# MakerstudioTrainingBoard.net
KiCad netlist of a schematic drawn in EAGLE
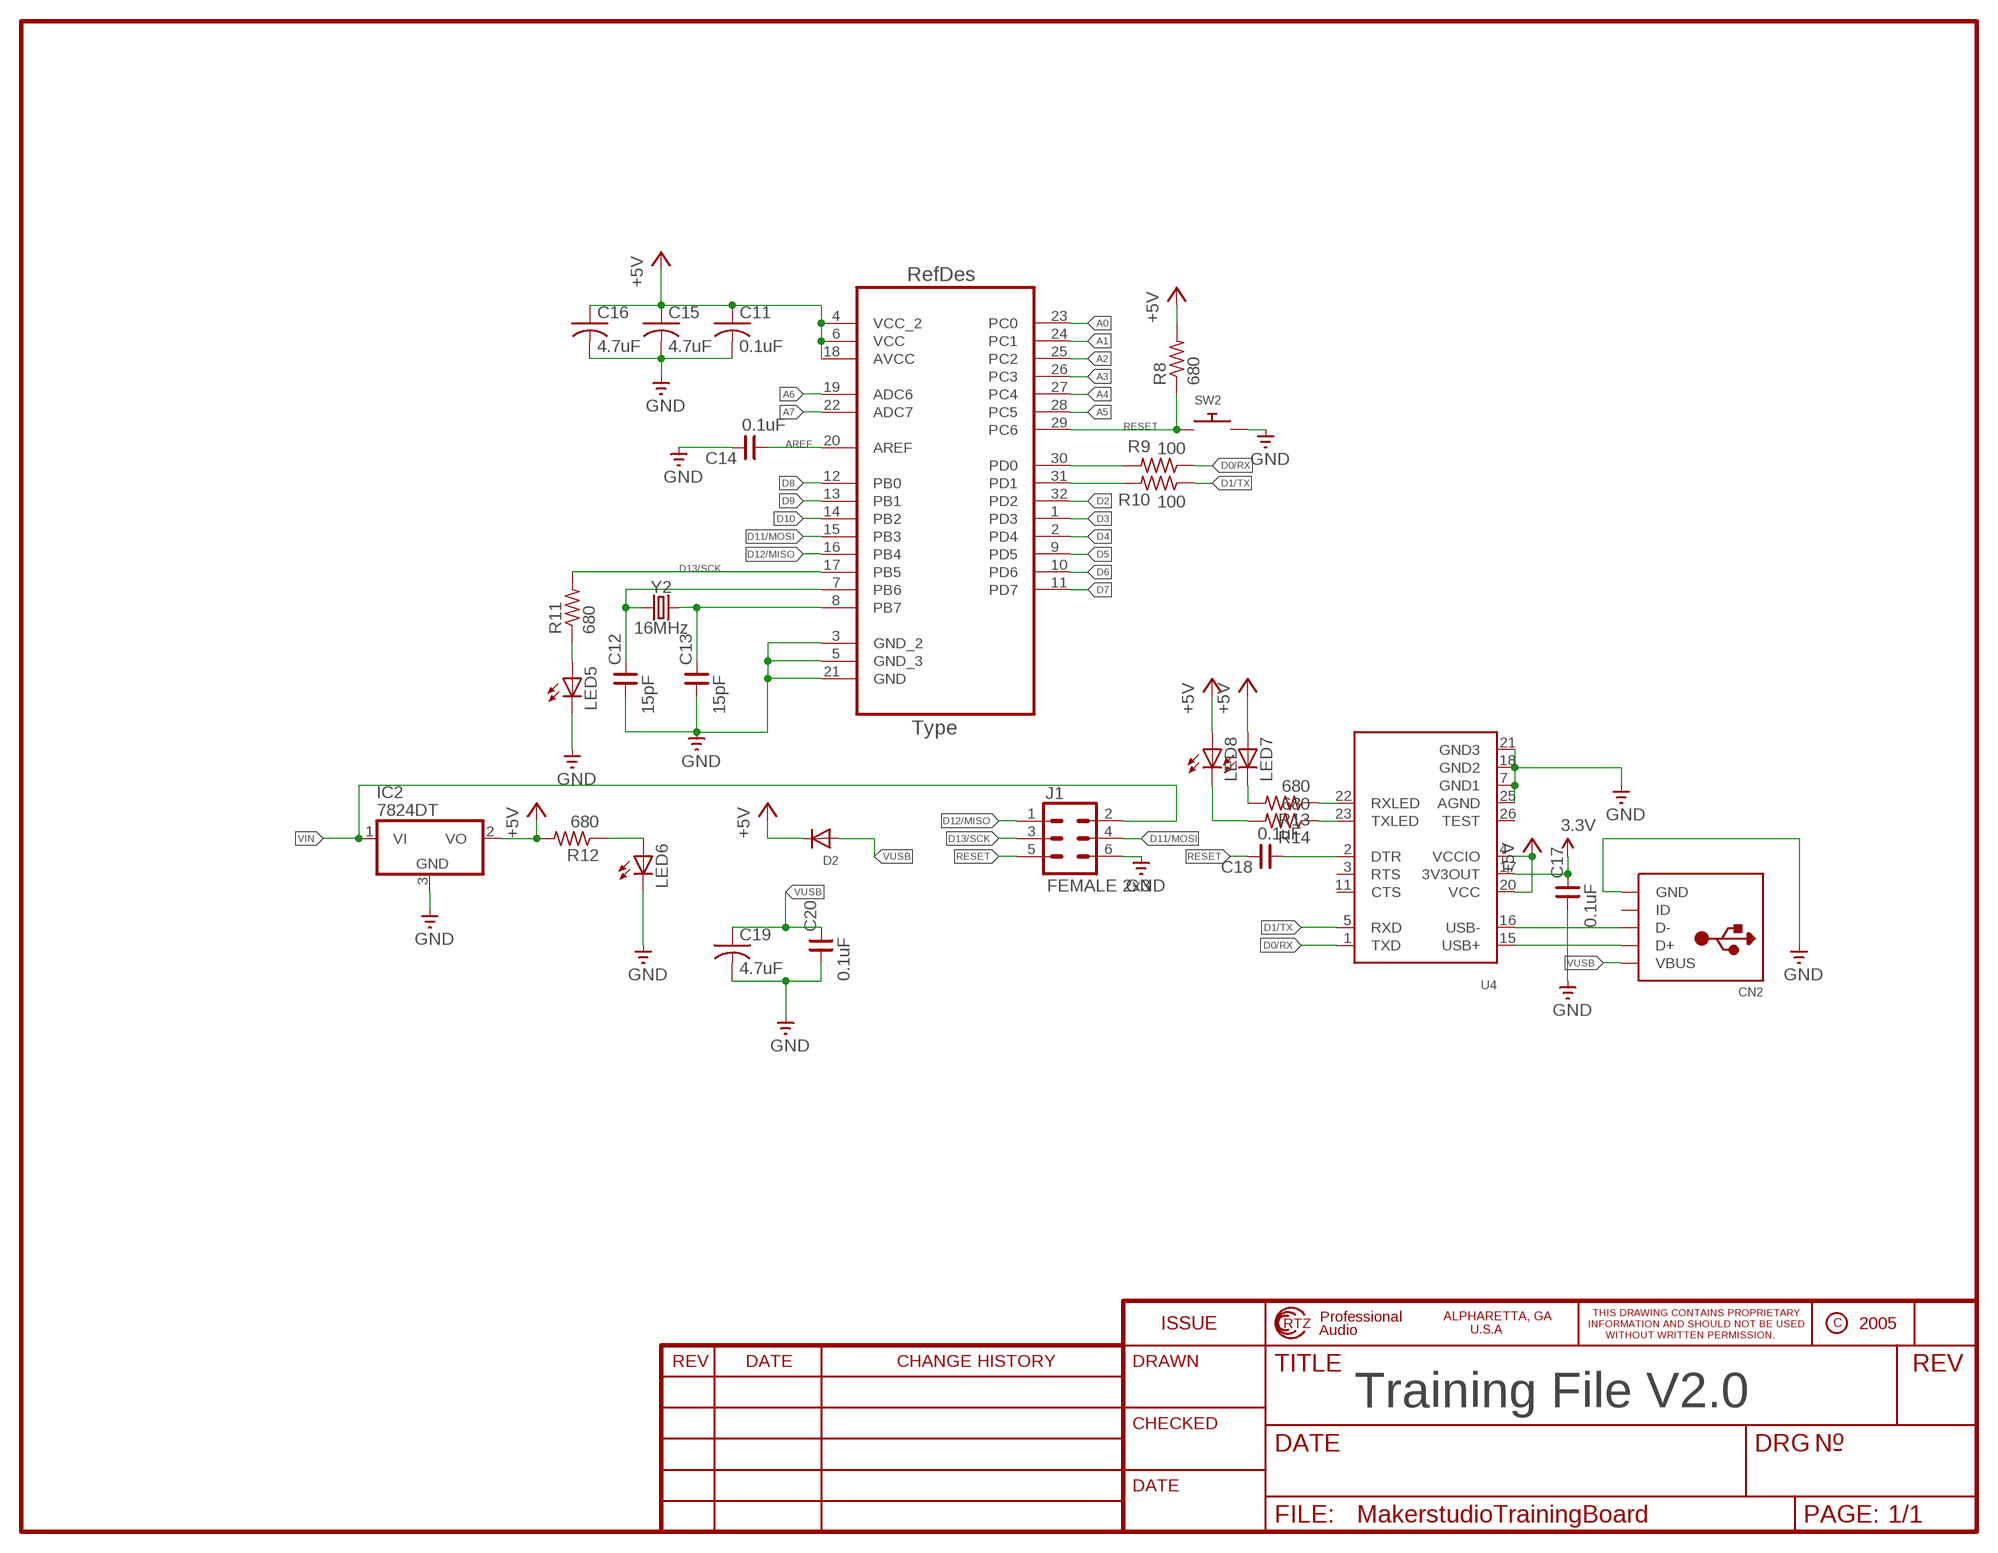
[diagram p0: schematic, sheet 1]

(export (version "E")
  (design (tool "Eeschema 10.0.6"))
  (components
    (comp (ref "C11")
      (value "0.1uF")
      (footprint "eagle-import:C0805")
      (libsource (lib "eagle-import") (part "C-USC0805"))
    )
    (comp (ref "C12")
      (value "15pF")
      (footprint "eagle-import:0805")
      (libsource (lib "eagle-import") (part "CNP-0805"))
    )
    (comp (ref "C13")
      (value "15pF")
      (footprint "eagle-import:0805")
      (libsource (lib "eagle-import") (part "CNP-0805"))
    )
    (comp (ref "C14")
      (value "0.1uF")
      (footprint "eagle-import:0805")
      (libsource (lib "eagle-import") (part "CNP-0805"))
    )
    (comp (ref "C15")
      (value "4.7uF")
      (footprint "eagle-import:C0805")
      (libsource (lib "eagle-import") (part "C-USC0805"))
    )
    (comp (ref "C16")
      (value "4.7uF")
      (footprint "eagle-import:C0805")
      (libsource (lib "eagle-import") (part "C-USC0805"))
    )
    (comp (ref "C17")
      (value "0.1uF")
      (footprint "eagle-import:0805")
      (libsource (lib "eagle-import") (part "CNP-0805"))
    )
    (comp (ref "C18")
      (value "0.1uF")
      (footprint "eagle-import:0805")
      (libsource (lib "eagle-import") (part "CNP-0805"))
    )
    (comp (ref "C19")
      (value "4.7uF")
      (footprint "eagle-import:C0805")
      (libsource (lib "eagle-import") (part "C-USC0805"))
    )
    (comp (ref "C20")
      (value "0.1uF")
      (footprint "eagle-import:0805")
      (libsource (lib "eagle-import") (part "CNP-0805"))
    )
    (comp (ref "CN2")
      (value "USBMINIB")
      (footprint "eagle-import:USB-MINIB")
      (libsource (lib "eagle-import") (part "USBMINIB"))
    )
    (comp (ref "D2")
      (value "DIODESOD-123")
      (footprint "eagle-import:SOD-123")
      (libsource (lib "eagle-import") (part "DIODESOD-123"))
    )
    (comp (ref "IC2")
      (value "7824DT")
      (footprint "eagle-import:TO252")
      (libsource (lib "eagle-import") (part "78DT24"))
    )
    (comp (ref "J1")
      (value "FEMALE 2x3")
      (footprint "eagle-import:2X3")
      (libsource (lib "eagle-import") (part "CONN_03X2FEMALE"))
    )
    (comp (ref "LED5")
      (value "LEDCHIPLED_0805")
      (footprint "eagle-import:CHIPLED_0805")
      (libsource (lib "eagle-import") (part "LEDCHIPLED_0805"))
    )
    (comp (ref "LED6")
      (value "LEDCHIPLED_0805")
      (footprint "eagle-import:CHIPLED_0805")
      (libsource (lib "eagle-import") (part "LEDCHIPLED_0805"))
    )
    (comp (ref "LED7")
      (value "LEDCHIPLED_0805")
      (footprint "eagle-import:CHIPLED_0805")
      (libsource (lib "eagle-import") (part "LEDCHIPLED_0805"))
    )
    (comp (ref "LED8")
      (value "LEDCHIPLED_0805")
      (footprint "eagle-import:CHIPLED_0805")
      (libsource (lib "eagle-import") (part "LEDCHIPLED_0805"))
    )
    (comp (ref "R8")
      (value "680")
      (footprint "eagle-import:R0805")
      (libsource (lib "eagle-import") (part "R-US_R0805"))
    )
    (comp (ref "R9")
      (value "100")
      (footprint "eagle-import:R0805")
      (libsource (lib "eagle-import") (part "R-US_R0805"))
    )
    (comp (ref "R10")
      (value "100")
      (footprint "eagle-import:R0805")
      (libsource (lib "eagle-import") (part "R-US_R0805"))
    )
    (comp (ref "R11")
      (value "680")
      (footprint "eagle-import:R0805")
      (libsource (lib "eagle-import") (part "R-US_R0805"))
    )
    (comp (ref "R12")
      (value "680")
      (footprint "eagle-import:R0805")
      (libsource (lib "eagle-import") (part "R-US_R0805"))
    )
    (comp (ref "R13")
      (value "680")
      (footprint "eagle-import:R0805")
      (libsource (lib "eagle-import") (part "R-US_R0805"))
    )
    (comp (ref "R14")
      (value "680")
      (footprint "eagle-import:R0805")
      (libsource (lib "eagle-import") (part "R-US_R0805"))
    )
    (comp (ref "SW2")
      (value "SWITCH_PUSHBUTTONEVQ-PE")
      (footprint "eagle-import:TACT_PANA-EVQ")
      (libsource (lib "eagle-import") (part "SWITCH_PUSHBUTTONEVQ-PE"))
    )
    (comp (ref "U3")
      (value "ATMEGA328P-AU")
      (footprint "eagle-import:QFP80P900X900X120-32N")
      (libsource (lib "eagle-import") (part "ATMEGA328P-AU"))
    )
    (comp (ref "U4")
      (value "FT232RLSSOP28")
      (footprint "eagle-import:SSOP28DB")
      (libsource (lib "eagle-import") (part "FT232RLSSOP28"))
    )
    (comp (ref "Y2")
      (value "16MHz")
      (footprint "eagle-import:HC49US")
      (libsource (lib "eagle-import") (part "CRYSTAL-16MHZPTH-HC49US"))
    )
  )
  (nets
    (net (code "1") (name "+5V") (class "Default")
      (node (ref "C11") (pin "1") (pinfunction "1_1") (pintype "passive"))
      (node (ref "C15") (pin "1") (pinfunction "1_1") (pintype "passive"))
      (node (ref "C16") (pin "1") (pinfunction "1_1") (pintype "passive"))
      (node (ref "D2") (pin "C") (pinfunction "C_C") (pintype "passive"))
      (node (ref "IC2") (pin "2") (pinfunction "VO_2") (pintype "passive"))
      (node (ref "LED7") (pin "A") (pinfunction "A_A") (pintype "passive"))
      (node (ref "LED8") (pin "A") (pinfunction "A_A") (pintype "passive"))
      (node (ref "R12") (pin "2") (pinfunction "2_2") (pintype "passive"))
      (node (ref "R8") (pin "2") (pinfunction "2_2") (pintype "passive"))
      (node (ref "U3") (pin "18") (pinfunction "AVCC_18") (pintype "power_in"))
      (node (ref "U3") (pin "4") (pinfunction "VCC_2_4") (pintype "power_in"))
      (node (ref "U3") (pin "6") (pinfunction "VCC_6") (pintype "power_in"))
      (node (ref "U4") (pin "20") (pinfunction "VCC_20") (pintype "power_in"))
      (node (ref "U4") (pin "4") (pinfunction "VCCIO_4") (pintype "power_in"))
    )
    (net (code "2") (name "/AREF") (class "Default")
      (node (ref "C14") (pin "1") (pinfunction "1_1") (pintype "passive"))
      (node (ref "U3") (pin "20") (pinfunction "AREF_20") (pintype "input"))
    )
    (net (code "3") (name "3.3V") (class "Default")
      (node (ref "C17") (pin "2") (pinfunction "2_2") (pintype "passive"))
      (node (ref "U4") (pin "17") (pinfunction "3V3OUT_17") (pintype "power_in"))
    )
    (net (code "4") (name "A0") (class "Default")
      (node (ref "U3") (pin "23") (pinfunction "PC0_23") (pintype "bidirectional"))
    )
    (net (code "5") (name "A1") (class "Default")
      (node (ref "U3") (pin "24") (pinfunction "PC1_24") (pintype "bidirectional"))
    )
    (net (code "6") (name "A2") (class "Default")
      (node (ref "U3") (pin "25") (pinfunction "PC2_25") (pintype "bidirectional"))
    )
    (net (code "7") (name "A3") (class "Default")
      (node (ref "U3") (pin "26") (pinfunction "PC3_26") (pintype "bidirectional"))
    )
    (net (code "8") (name "A4") (class "Default")
      (node (ref "U3") (pin "27") (pinfunction "PC4_27") (pintype "bidirectional"))
    )
    (net (code "9") (name "A5") (class "Default")
      (node (ref "U3") (pin "28") (pinfunction "PC5_28") (pintype "bidirectional"))
    )
    (net (code "10") (name "A6") (class "Default")
      (node (ref "U3") (pin "19") (pinfunction "ADC6_19") (pintype "input"))
    )
    (net (code "11") (name "A7") (class "Default")
      (node (ref "U3") (pin "22") (pinfunction "ADC7_22") (pintype "input"))
    )
    (net (code "12") (name "D0{slash}RX") (class "Default")
      (node (ref "R9") (pin "1") (pinfunction "1_1") (pintype "passive"))
      (node (ref "U4") (pin "1") (pinfunction "TXD_1") (pintype "output"))
    )
    (net (code "13") (name "D1{slash}TX") (class "Default")
      (node (ref "R10") (pin "1") (pinfunction "1_1") (pintype "passive"))
      (node (ref "U4") (pin "5") (pinfunction "RXD_5") (pintype "input"))
    )
    (net (code "14") (name "D2") (class "Default")
      (node (ref "U3") (pin "32") (pinfunction "PD2_32") (pintype "bidirectional"))
    )
    (net (code "15") (name "D3") (class "Default")
      (node (ref "U3") (pin "1") (pinfunction "PD3_1") (pintype "bidirectional"))
    )
    (net (code "16") (name "D4") (class "Default")
      (node (ref "U3") (pin "2") (pinfunction "PD4_2") (pintype "bidirectional"))
    )
    (net (code "17") (name "D5") (class "Default")
      (node (ref "U3") (pin "9") (pinfunction "PD5_9") (pintype "bidirectional"))
    )
    (net (code "18") (name "D6") (class "Default")
      (node (ref "U3") (pin "10") (pinfunction "PD6_10") (pintype "bidirectional"))
    )
    (net (code "19") (name "D7") (class "Default")
      (node (ref "U3") (pin "11") (pinfunction "PD7_11") (pintype "bidirectional"))
    )
    (net (code "20") (name "D8") (class "Default")
      (node (ref "U3") (pin "12") (pinfunction "PB0_12") (pintype "bidirectional"))
    )
    (net (code "21") (name "D9") (class "Default")
      (node (ref "U3") (pin "13") (pinfunction "PB1_13") (pintype "bidirectional"))
    )
    (net (code "22") (name "D10") (class "Default")
      (node (ref "U3") (pin "14") (pinfunction "PB2_14") (pintype "bidirectional"))
    )
    (net (code "23") (name "D11{slash}MOSI") (class "Default")
      (node (ref "J1") (pin "4") (pinfunction "4_4") (pintype "bidirectional"))
      (node (ref "U3") (pin "15") (pinfunction "PB3_15") (pintype "bidirectional"))
    )
    (net (code "24") (name "D12{slash}MISO") (class "Default")
      (node (ref "J1") (pin "1") (pinfunction "1_1") (pintype "bidirectional"))
      (node (ref "U3") (pin "16") (pinfunction "PB4_16") (pintype "bidirectional"))
    )
    (net (code "25") (name "D13{slash}SCK") (class "Default")
      (node (ref "J1") (pin "3") (pinfunction "3_3") (pintype "bidirectional"))
      (node (ref "R11") (pin "2") (pinfunction "2_2") (pintype "passive"))
      (node (ref "U3") (pin "17") (pinfunction "PB5_17") (pintype "bidirectional"))
    )
    (net (code "26") (name "GND") (class "Default")
      (node (ref "C11") (pin "2") (pinfunction "2_2") (pintype "passive"))
      (node (ref "C12") (pin "1") (pinfunction "1_1") (pintype "passive"))
      (node (ref "C13") (pin "1") (pinfunction "1_1") (pintype "passive"))
      (node (ref "C14") (pin "2") (pinfunction "2_2") (pintype "passive"))
      (node (ref "C15") (pin "2") (pinfunction "2_2") (pintype "passive"))
      (node (ref "C16") (pin "2") (pinfunction "2_2") (pintype "passive"))
      (node (ref "C17") (pin "1") (pinfunction "1_1") (pintype "passive"))
      (node (ref "C19") (pin "2") (pinfunction "2_2") (pintype "passive"))
      (node (ref "C20") (pin "1") (pinfunction "1_1") (pintype "passive"))
      (node (ref "CN2") (pin "GND") (pinfunction "GND_GND") (pintype "power_in"))
      (node (ref "IC2") (pin "3") (pinfunction "GND_3") (pintype "passive"))
      (node (ref "J1") (pin "6") (pinfunction "6_6") (pintype "bidirectional"))
      (node (ref "LED5") (pin "C") (pinfunction "C_C") (pintype "passive"))
      (node (ref "LED6") (pin "C") (pinfunction "C_C") (pintype "passive"))
      (node (ref "SW2") (pin "P$2") (pinfunction "P$2_P$2") (pintype "passive"))
      (node (ref "U3") (pin "21") (pinfunction "GND_21") (pintype "passive"))
      (node (ref "U3") (pin "3") (pinfunction "GND_2_3") (pintype "passive"))
      (node (ref "U3") (pin "5") (pinfunction "GND_3_5") (pintype "passive"))
      (node (ref "U4") (pin "18") (pinfunction "GND2_18") (pintype "power_in"))
      (node (ref "U4") (pin "21") (pinfunction "GND3_21") (pintype "power_in"))
      (node (ref "U4") (pin "25") (pinfunction "AGND_25") (pintype "power_in"))
      (node (ref "U4") (pin "7") (pinfunction "GND1_7") (pintype "power_in"))
    )
    (net (code "27") (name "Net-(LED5-PadA)") (class "Default")
      (node (ref "LED5") (pin "A") (pinfunction "A_A") (pintype "passive"))
      (node (ref "R11") (pin "1") (pinfunction "1_1") (pintype "passive"))
    )
    (net (code "28") (name "Net-(LED6-PadA)") (class "Default")
      (node (ref "LED6") (pin "A") (pinfunction "A_A") (pintype "passive"))
      (node (ref "R12") (pin "1") (pinfunction "1_1") (pintype "passive"))
    )
    (net (code "29") (name "Net-(LED7-PadC)") (class "Default")
      (node (ref "LED7") (pin "C") (pinfunction "C_C") (pintype "passive"))
      (node (ref "R13") (pin "2") (pinfunction "2_2") (pintype "passive"))
    )
    (net (code "30") (name "Net-(LED8-PadC)") (class "Default")
      (node (ref "LED8") (pin "C") (pinfunction "C_C") (pintype "passive"))
      (node (ref "R14") (pin "2") (pinfunction "2_2") (pintype "passive"))
    )
    (net (code "31") (name "Net-(U3-PB6)") (class "Default")
      (node (ref "C12") (pin "2") (pinfunction "2_2") (pintype "passive"))
      (node (ref "U3") (pin "7") (pinfunction "PB6_7") (pintype "bidirectional"))
      (node (ref "Y2") (pin "1") (pinfunction "1_1") (pintype "passive"))
    )
    (net (code "32") (name "Net-(U3-PB7)") (class "Default")
      (node (ref "C13") (pin "2") (pinfunction "2_2") (pintype "passive"))
      (node (ref "U3") (pin "8") (pinfunction "PB7_8") (pintype "bidirectional"))
      (node (ref "Y2") (pin "2") (pinfunction "2_2") (pintype "passive"))
    )
    (net (code "33") (name "Net-(U3-PD0)") (class "Default")
      (node (ref "R9") (pin "2") (pinfunction "2_2") (pintype "passive"))
      (node (ref "U3") (pin "30") (pinfunction "PD0_30") (pintype "bidirectional"))
    )
    (net (code "34") (name "Net-(U3-PD1)") (class "Default")
      (node (ref "R10") (pin "2") (pinfunction "2_2") (pintype "passive"))
      (node (ref "U3") (pin "31") (pinfunction "PD1_31") (pintype "bidirectional"))
    )
    (net (code "35") (name "Net-(U4-DTR)") (class "Default")
      (node (ref "C18") (pin "1") (pinfunction "1_1") (pintype "passive"))
      (node (ref "U4") (pin "2") (pinfunction "DTR_2") (pintype "bidirectional"))
    )
    (net (code "36") (name "Net-(U4-RXLED)") (class "Default")
      (node (ref "R13") (pin "1") (pinfunction "1_1") (pintype "passive"))
      (node (ref "U4") (pin "22") (pinfunction "RXLED_22") (pintype "bidirectional"))
    )
    (net (code "37") (name "Net-(U4-TXLED)") (class "Default")
      (node (ref "R14") (pin "1") (pinfunction "1_1") (pintype "passive"))
      (node (ref "U4") (pin "23") (pinfunction "TXLED_23") (pintype "bidirectional"))
    )
    (net (code "38") (name "Net-(U4-USB+)") (class "Default")
      (node (ref "CN2") (pin "D+") (pinfunction "D+_D+") (pintype "bidirectional"))
      (node (ref "U4") (pin "15") (pinfunction "USB+_15") (pintype "bidirectional"))
    )
    (net (code "39") (name "Net-(U4-USB-)") (class "Default")
      (node (ref "CN2") (pin "D-") (pinfunction "D-_D-") (pintype "bidirectional"))
      (node (ref "U4") (pin "16") (pinfunction "USB-_16") (pintype "bidirectional"))
    )
    (net (code "40") (name "RESET") (class "Default")
      (node (ref "C18") (pin "2") (pinfunction "2_2") (pintype "passive"))
      (node (ref "J1") (pin "5") (pinfunction "5_5") (pintype "bidirectional"))
      (node (ref "R8") (pin "1") (pinfunction "1_1") (pintype "passive"))
      (node (ref "SW2") (pin "P$1") (pinfunction "P$1_P$1") (pintype "passive"))
      (node (ref "U3") (pin "29") (pinfunction "PC6_29") (pintype "bidirectional"))
    )
    (net (code "41") (name "VIN") (class "Default")
      (node (ref "IC2") (pin "1") (pinfunction "VI_1") (pintype "input"))
      (node (ref "J1") (pin "2") (pinfunction "2_2") (pintype "bidirectional"))
    )
    (net (code "42") (name "VUSB") (class "Default")
      (node (ref "C19") (pin "1") (pinfunction "1_1") (pintype "passive"))
      (node (ref "C20") (pin "2") (pinfunction "2_2") (pintype "passive"))
      (node (ref "CN2") (pin "VBUS") (pinfunction "VBUS_VBUS") (pintype "power_in"))
      (node (ref "D2") (pin "A") (pinfunction "A_A") (pintype "passive"))
    )
    (net (code "43") (name "unconnected-(CN2-PadID)") (class "Default")
      (node (ref "CN2") (pin "ID") (pinfunction "ID_ID") (pintype "bidirectional"))
    )
    (net (code "44") (name "unconnected-(U4-CTS-Pad11)") (class "Default")
      (node (ref "U4") (pin "11") (pinfunction "CTS_11") (pintype "bidirectional"))
    )
    (net (code "45") (name "unconnected-(U4-RTS-Pad3)") (class "Default")
      (node (ref "U4") (pin "3") (pinfunction "RTS_3") (pintype "bidirectional"))
    )
    (net (code "46") (name "unconnected-(U4-TEST-Pad26)") (class "Default")
      (node (ref "U4") (pin "26") (pinfunction "TEST_26") (pintype "input"))
    )
  )
)
